# SingleSystem.net
KiCad netlist of a schematic drawn in EAGLE
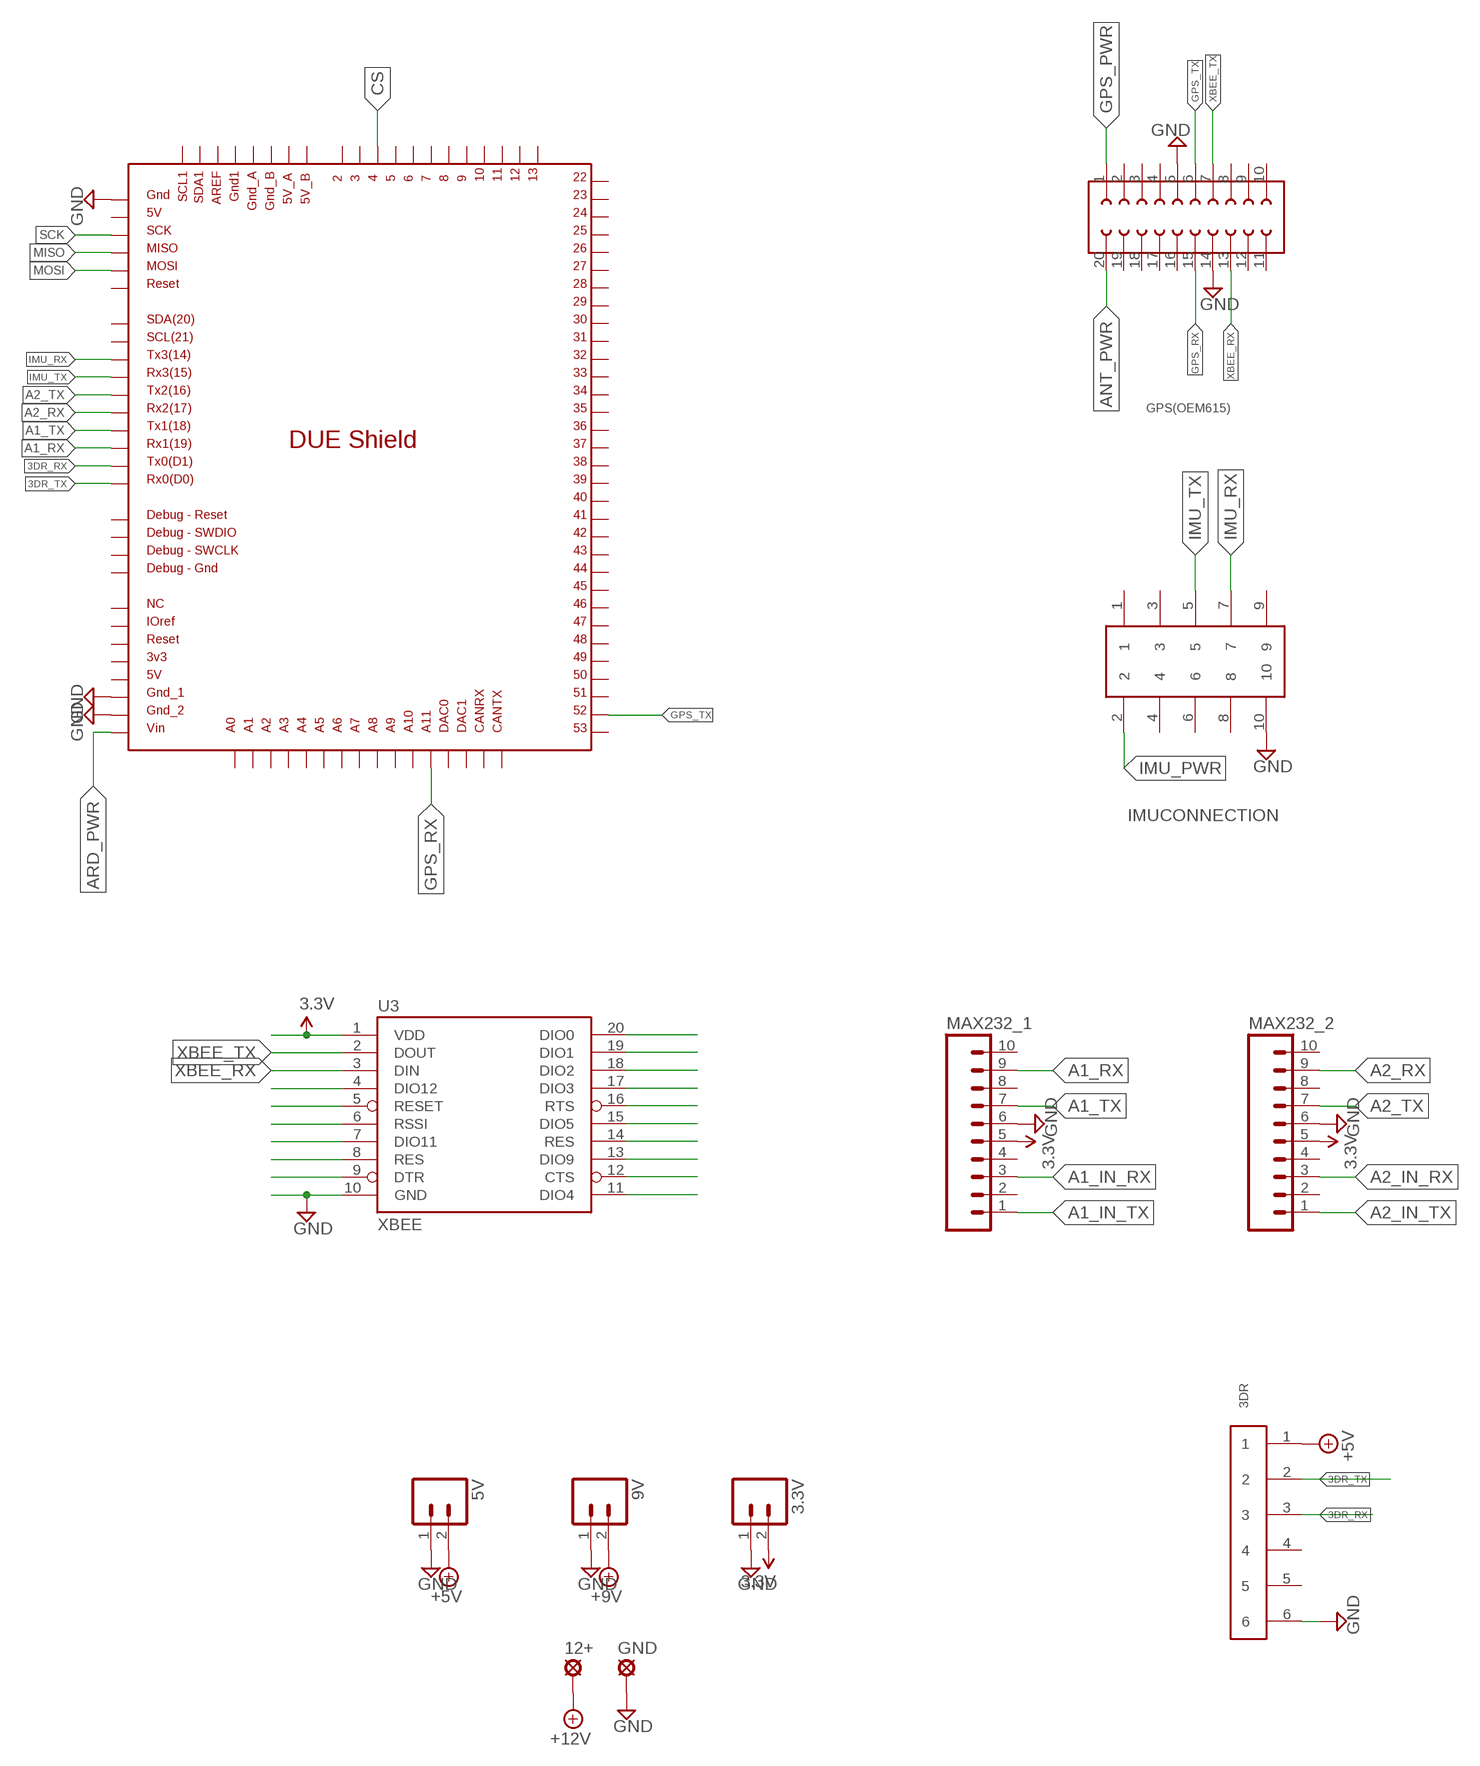
[diagram p0: schematic, sheet 1, part 1 of 2]
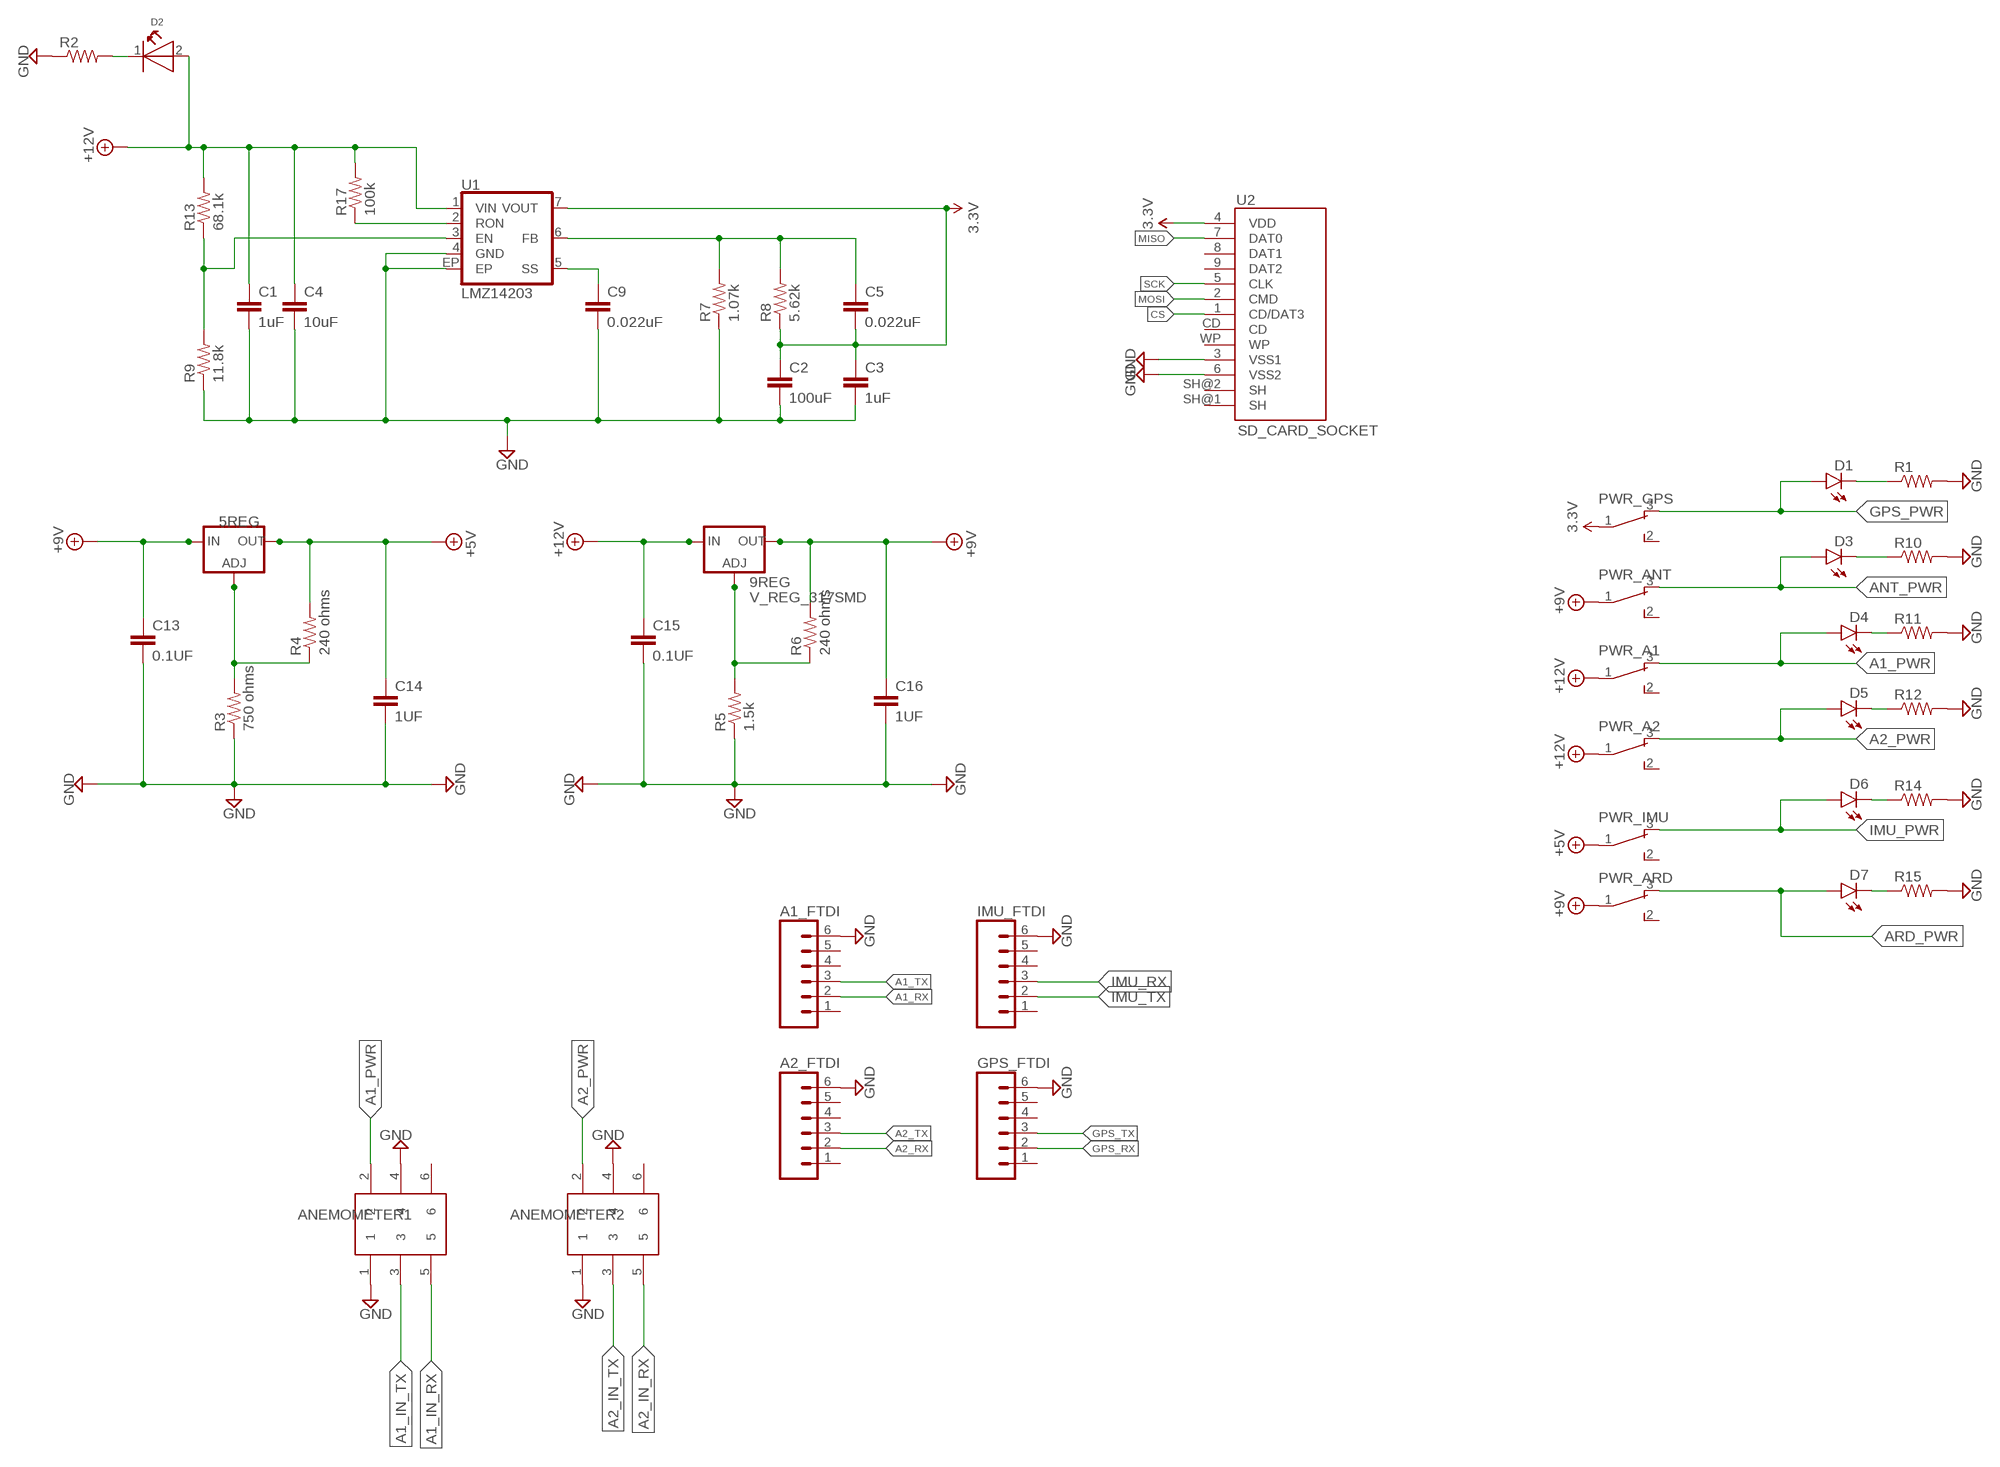
[diagram p1: schematic, sheet 1, part 2 of 2]

(export (version "E")
  (design (tool "Eeschema 10.0.6"))
  (components
    (comp (ref "3.3V")
      (value "M02")
      (footprint "eagle-import:02P")
      (libsource (lib "eagle-import") (part "M02"))
    )
    (comp (ref "3DR")
      (value "653006114822")
      (footprint "eagle-import:653006114822")
      (libsource (lib "eagle-import") (part "653006114822"))
    )
    (comp (ref "5REG")
      (value "V_REG_317SMD")
      (footprint "eagle-import:SOT223")
      (libsource (lib "eagle-import") (part "V_REG_317SMD"))
    )
    (comp (ref "5V")
      (value "M02")
      (footprint "eagle-import:02P")
      (libsource (lib "eagle-import") (part "M02"))
    )
    (comp (ref "9REG")
      (value "V_REG_317SMD")
      (footprint "eagle-import:SOT223")
      (libsource (lib "eagle-import") (part "V_REG_317SMD"))
    )
    (comp (ref "9V")
      (value "M02")
      (footprint "eagle-import:02P")
      (libsource (lib "eagle-import") (part "M02"))
    )
    (comp (ref "12+")
      (value "SE14")
      (footprint "eagle-import:SE14")
      (libsource (lib "eagle-import") (part "SE14"))
    )
    (comp (ref "A1_FTDI")
      (value "M06")
      (footprint "eagle-import:06P")
      (libsource (lib "eagle-import") (part "M06"))
    )
    (comp (ref "A2_FTDI")
      (value "M06")
      (footprint "eagle-import:06P")
      (libsource (lib "eagle-import") (part "M06"))
    )
    (comp (ref "ANEMOMETER1")
      (value "61200622323")
      (footprint "eagle-import:61200622323")
      (libsource (lib "eagle-import") (part "61200622323"))
    )
    (comp (ref "ANEMOMETER2")
      (value "61200622323")
      (footprint "eagle-import:61200622323")
      (libsource (lib "eagle-import") (part "61200622323"))
    )
    (comp (ref "C1")
      (value "1uF")
      (footprint "eagle-import:0805")
      (fields (field (name "MF") "VISHAY/SPRAGUE") (field (name "MPN") "1C10Z5U104M050R"))
      (libsource (lib "eagle-import") (part "1UF-25V-10%(0805)"))
    )
    (comp (ref "C2")
      (value "100uF")
      (footprint "eagle-import:1206")
      (libsource (lib "eagle-import") (part "CAP1206"))
    )
    (comp (ref "C3")
      (value "1uF")
      (footprint "eagle-import:0805")
      (fields (field (name "MF") "VISHAY/SPRAGUE") (field (name "MPN") "1C10Z5U104M050R"))
      (libsource (lib "eagle-import") (part "1UF-25V-10%(0805)"))
    )
    (comp (ref "C4")
      (value "10uF")
      (footprint "eagle-import:0805")
      (libsource (lib "eagle-import") (part "CAP0805"))
    )
    (comp (ref "C5")
      (value "0.022uF")
      (footprint "eagle-import:0603-CAP")
      (libsource (lib "eagle-import") (part "CAP0603-CAP"))
    )
    (comp (ref "C9")
      (value "0.022uF")
      (footprint "eagle-import:0603-CAP")
      (libsource (lib "eagle-import") (part "CAP0603-CAP"))
    )
    (comp (ref "C13")
      (value "0.1UF")
      (footprint "eagle-import:0805")
      (libsource (lib "eagle-import") (part "1UF-25V-10%(0805)"))
    )
    (comp (ref "C14")
      (value "1UF")
      (footprint "eagle-import:0805")
      (libsource (lib "eagle-import") (part "1UF-25V-10%(0805)"))
    )
    (comp (ref "C15")
      (value "0.1UF")
      (footprint "eagle-import:0805")
      (libsource (lib "eagle-import") (part "1UF-25V-10%(0805)"))
    )
    (comp (ref "C16")
      (value "1UF")
      (footprint "eagle-import:0805")
      (libsource (lib "eagle-import") (part "1UF-25V-10%(0805)"))
    )
    (comp (ref "D1")
      (value "LED-FKIT-1206")
      (footprint "eagle-import:FKIT-LED-1206")
      (libsource (lib "eagle-import") (part "LED-FKIT-1206"))
    )
    (comp (ref "D2")
      (value "WL-SMCW-150120BS75000-B")
      (footprint "eagle-import:1206")
      (fields
        (field (name "MANUFACTURER") "Würth Elektronik eiSos GmbH")
        (field (name "CREATED-BY") "Christin Otto")
      )
      (libsource (lib "eagle-import") (part "WL-SMCW-150120BS75000-B"))
    )
    (comp (ref "D3")
      (value "LED-FKIT-1206")
      (footprint "eagle-import:FKIT-LED-1206")
      (libsource (lib "eagle-import") (part "LED-FKIT-1206"))
    )
    (comp (ref "D4")
      (value "LED-FKIT-1206")
      (footprint "eagle-import:FKIT-LED-1206")
      (libsource (lib "eagle-import") (part "LED-FKIT-1206"))
    )
    (comp (ref "D5")
      (value "LED-FKIT-1206")
      (footprint "eagle-import:FKIT-LED-1206")
      (libsource (lib "eagle-import") (part "LED-FKIT-1206"))
    )
    (comp (ref "D6")
      (value "LED-FKIT-1206")
      (footprint "eagle-import:FKIT-LED-1206")
      (libsource (lib "eagle-import") (part "LED-FKIT-1206"))
    )
    (comp (ref "D7")
      (value "LED-FKIT-1206")
      (footprint "eagle-import:FKIT-LED-1206")
      (libsource (lib "eagle-import") (part "LED-FKIT-1206"))
    )
    (comp (ref "GND")
      (value "SE14")
      (footprint "eagle-import:SE14")
      (libsource (lib "eagle-import") (part "SE14"))
    )
    (comp (ref "GPS(OEM615)")
      (value "62002021821")
      (footprint "eagle-import:62002021821")
      (libsource (lib "eagle-import") (part "62002021821"))
    )
    (comp (ref "GPS_FTDI")
      (value "M06")
      (footprint "eagle-import:06P")
      (libsource (lib "eagle-import") (part "M06"))
    )
    (comp (ref "IMUCONNECTION")
      (value "62501021621")
      (footprint "eagle-import:62501021621")
      (libsource (lib "eagle-import") (part "62501021621"))
    )
    (comp (ref "IMU_FTDI")
      (value "M06")
      (footprint "eagle-import:06P")
      (libsource (lib "eagle-import") (part "M06"))
    )
    (comp (ref "MAX232_1")
      (value "M10")
      (footprint "eagle-import:10P")
      (libsource (lib "eagle-import") (part "M10"))
    )
    (comp (ref "MAX232_2")
      (value "M10")
      (footprint "eagle-import:10P")
      (libsource (lib "eagle-import") (part "M10"))
    )
    (comp (ref "PWR_A1")
      (value "450301014042")
      (footprint "eagle-import:450301014042")
      (libsource (lib "eagle-import") (part "450301014042"))
    )
    (comp (ref "PWR_A2")
      (value "450301014042")
      (footprint "eagle-import:450301014042")
      (libsource (lib "eagle-import") (part "450301014042"))
    )
    (comp (ref "PWR_ANT")
      (value "450301014042")
      (footprint "eagle-import:450301014042")
      (libsource (lib "eagle-import") (part "450301014042"))
    )
    (comp (ref "PWR_ARD")
      (value "450301014042")
      (footprint "eagle-import:450301014042")
      (libsource (lib "eagle-import") (part "450301014042"))
    )
    (comp (ref "PWR_GPS")
      (value "450301014042")
      (footprint "eagle-import:450301014042")
      (libsource (lib "eagle-import") (part "450301014042"))
    )
    (comp (ref "PWR_IMU")
      (value "450301014042")
      (footprint "eagle-import:450301014042")
      (libsource (lib "eagle-import") (part "450301014042"))
    )
    (comp (ref "R1")
      (value "R-US_M2012")
      (footprint "eagle-import:M2012")
      (libsource (lib "eagle-import") (part "R-US_M2012"))
    )
    (comp (ref "R2")
      (value "R-US_M2012")
      (footprint "eagle-import:M2012")
      (libsource (lib "eagle-import") (part "resistor_R-US_M2012"))
    )
    (comp (ref "R3")
      (value "750 ohms")
      (footprint "eagle-import:M2012")
      (libsource (lib "eagle-import") (part "R-US_M2012"))
    )
    (comp (ref "R4")
      (value "240 ohms")
      (footprint "eagle-import:M2012")
      (libsource (lib "eagle-import") (part "R-US_M2012"))
    )
    (comp (ref "R5")
      (value "1.5k")
      (footprint "eagle-import:M2012")
      (libsource (lib "eagle-import") (part "R-US_M2012"))
    )
    (comp (ref "R6")
      (value "240 ohms")
      (footprint "eagle-import:M2012")
      (libsource (lib "eagle-import") (part "R-US_M2012"))
    )
    (comp (ref "R7")
      (value "1.07k")
      (footprint "eagle-import:M2012")
      (libsource (lib "eagle-import") (part "resistor_R-US_M2012"))
    )
    (comp (ref "R8")
      (value "5.62k")
      (footprint "eagle-import:M2012")
      (libsource (lib "eagle-import") (part "resistor_R-US_M2012"))
    )
    (comp (ref "R9")
      (value "11.8k")
      (footprint "eagle-import:M2012")
      (libsource (lib "eagle-import") (part "resistor_R-US_M2012"))
    )
    (comp (ref "R10")
      (value "R-US_M2012")
      (footprint "eagle-import:M2012")
      (libsource (lib "eagle-import") (part "R-US_M2012"))
    )
    (comp (ref "R11")
      (value "R-US_M2012")
      (footprint "eagle-import:M2012")
      (libsource (lib "eagle-import") (part "R-US_M2012"))
    )
    (comp (ref "R12")
      (value "R-US_M2012")
      (footprint "eagle-import:M2012")
      (libsource (lib "eagle-import") (part "R-US_M2012"))
    )
    (comp (ref "R13")
      (value "68.1k")
      (footprint "eagle-import:M2012")
      (libsource (lib "eagle-import") (part "resistor_R-US_M2012"))
    )
    (comp (ref "R14")
      (value "R-US_M2012")
      (footprint "eagle-import:M2012")
      (libsource (lib "eagle-import") (part "R-US_M2012"))
    )
    (comp (ref "R15")
      (value "R-US_M2012")
      (footprint "eagle-import:M2012")
      (libsource (lib "eagle-import") (part "resistor_R-US_M2012"))
    )
    (comp (ref "R17")
      (value "100k")
      (footprint "eagle-import:M2012")
      (libsource (lib "eagle-import") (part "resistor_R-US_M2012"))
    )
    (comp (ref "U$1")
      (value "DUE(NORMAL)")
      (footprint "eagle-import:DUE(NORMAL)")
      (libsource (lib "eagle-import") (part "DUE(NORMAL)"))
    )
    (comp (ref "U1")
      (value "LMZ14203")
      (footprint "eagle-import:TO-PMOD-7")
      (libsource (lib "eagle-import") (part "LMZ14203"))
    )
    (comp (ref "U2")
      (value "SD_CARD_SOCKET")
      (footprint "eagle-import:SD_1_1")
      (libsource (lib "eagle-import") (part "SD_CARD_SOCKET"))
    )
    (comp (ref "U3")
      (value "XBEE")
      (footprint "eagle-import:XBEE-1")
      (libsource (lib "eagle-import") (part "XBEE-1B1"))
    )
  )
  (nets
    (net (code "1") (name "+5V") (class "Default")
      (node (ref "3DR") (pin "1") (pinfunction "1_1") (pintype "passive"))
      (node (ref "5REG") (pin "2") (pinfunction "OUT_2") (pintype "output"))
      (node (ref "5V") (pin "2") (pinfunction "2_2") (pintype "passive"))
      (node (ref "C14") (pin "1") (pinfunction "1_1") (pintype "passive"))
      (node (ref "PWR_IMU") (pin "1") (pinfunction "1_1") (pintype "passive"))
      (node (ref "R4") (pin "2") (pinfunction "2_2") (pintype "passive"))
    )
    (net (code "2") (name "+9V") (class "Default")
      (node (ref "5REG") (pin "3") (pinfunction "IN_3") (pintype "input"))
      (node (ref "9REG") (pin "2") (pinfunction "OUT_2") (pintype "output"))
      (node (ref "9V") (pin "2") (pinfunction "2_2") (pintype "passive"))
      (node (ref "C13") (pin "1") (pinfunction "1_1") (pintype "passive"))
      (node (ref "C16") (pin "1") (pinfunction "1_1") (pintype "passive"))
      (node (ref "PWR_ANT") (pin "1") (pinfunction "1_1") (pintype "passive"))
      (node (ref "PWR_ARD") (pin "1") (pinfunction "1_1") (pintype "passive"))
      (node (ref "R6") (pin "2") (pinfunction "2_2") (pintype "passive"))
    )
    (net (code "3") (name "+12V") (class "Default")
      (node (ref "12+") (pin "MP") (pinfunction "MP_MP") (pintype "passive"))
      (node (ref "9REG") (pin "3") (pinfunction "IN_3") (pintype "input"))
      (node (ref "C1") (pin "1") (pinfunction "1_1") (pintype "passive"))
      (node (ref "C15") (pin "1") (pinfunction "1_1") (pintype "passive"))
      (node (ref "C4") (pin "1") (pinfunction "1_1") (pintype "passive"))
      (node (ref "D2") (pin "2") (pinfunction "A_2") (pintype "bidirectional"))
      (node (ref "PWR_A1") (pin "1") (pinfunction "1_1") (pintype "passive"))
      (node (ref "PWR_A2") (pin "1") (pinfunction "1_1") (pintype "passive"))
      (node (ref "R13") (pin "2") (pinfunction "2_2") (pintype "passive"))
      (node (ref "R17") (pin "2") (pinfunction "2_2") (pintype "passive"))
      (node (ref "U1") (pin "1") (pinfunction "VIN_1") (pintype "bidirectional"))
    )
    (net (code "4") (name "3.3V") (class "Default")
      (node (ref "3.3V") (pin "2") (pinfunction "2_2") (pintype "passive"))
      (node (ref "C2") (pin "1") (pinfunction "1_1") (pintype "passive"))
      (node (ref "C3") (pin "1") (pinfunction "1_1") (pintype "passive"))
      (node (ref "C5") (pin "2") (pinfunction "2_2") (pintype "passive"))
      (node (ref "MAX232_1") (pin "5") (pinfunction "5_5") (pintype "passive"))
      (node (ref "MAX232_2") (pin "5") (pinfunction "5_5") (pintype "passive"))
      (node (ref "PWR_GPS") (pin "1") (pinfunction "1_1") (pintype "passive"))
      (node (ref "R8") (pin "1") (pinfunction "1_1") (pintype "passive"))
      (node (ref "U1") (pin "7") (pinfunction "VOUT_7") (pintype "bidirectional"))
      (node (ref "U2") (pin "4") (pinfunction "VDD_4") (pintype "power_in"))
      (node (ref "U3") (pin "1") (pinfunction "VDD_1") (pintype "power_in"))
    )
    (net (code "5") (name "3DR_RX") (class "Default")
      (node (ref "3DR") (pin "3") (pinfunction "3_3") (pintype "passive"))
      (node (ref "U$1") (pin "TX0") (pinfunction "TX0_TX0") (pintype "bidirectional"))
    )
    (net (code "6") (name "3DR_TX") (class "Default")
      (node (ref "3DR") (pin "2") (pinfunction "2_2") (pintype "passive"))
      (node (ref "U$1") (pin "RX0") (pinfunction "RX0_RX0") (pintype "bidirectional"))
    )
    (net (code "7") (name "A1_IN_RX") (class "Default")
      (node (ref "ANEMOMETER1") (pin "5") (pinfunction "5_5") (pintype "passive"))
      (node (ref "MAX232_1") (pin "3") (pinfunction "3_3") (pintype "passive"))
    )
    (net (code "8") (name "A1_IN_TX") (class "Default")
      (node (ref "ANEMOMETER1") (pin "3") (pinfunction "3_3") (pintype "passive"))
      (node (ref "MAX232_1") (pin "1") (pinfunction "1_1") (pintype "passive"))
    )
    (net (code "9") (name "A1_PWR") (class "Default")
      (node (ref "ANEMOMETER1") (pin "2") (pinfunction "2_2") (pintype "passive"))
      (node (ref "D4") (pin "A") (pinfunction "A_A") (pintype "passive"))
      (node (ref "PWR_A1") (pin "3") (pinfunction "3_3") (pintype "passive"))
    )
    (net (code "10") (name "A1_RX") (class "Default")
      (node (ref "A1_FTDI") (pin "2") (pinfunction "2_2") (pintype "passive"))
      (node (ref "MAX232_1") (pin "9") (pinfunction "9_9") (pintype "passive"))
      (node (ref "U$1") (pin "RX1") (pinfunction "RX1_RX1") (pintype "bidirectional"))
    )
    (net (code "11") (name "A1_TX") (class "Default")
      (node (ref "A1_FTDI") (pin "3") (pinfunction "3_3") (pintype "passive"))
      (node (ref "MAX232_1") (pin "7") (pinfunction "7_7") (pintype "passive"))
      (node (ref "U$1") (pin "TX1") (pinfunction "TX1_TX1") (pintype "bidirectional"))
    )
    (net (code "12") (name "A2_IN_RX") (class "Default")
      (node (ref "ANEMOMETER2") (pin "5") (pinfunction "5_5") (pintype "passive"))
      (node (ref "MAX232_2") (pin "3") (pinfunction "3_3") (pintype "passive"))
    )
    (net (code "13") (name "A2_IN_TX") (class "Default")
      (node (ref "ANEMOMETER2") (pin "3") (pinfunction "3_3") (pintype "passive"))
      (node (ref "MAX232_2") (pin "1") (pinfunction "1_1") (pintype "passive"))
    )
    (net (code "14") (name "A2_PWR") (class "Default")
      (node (ref "ANEMOMETER2") (pin "2") (pinfunction "2_2") (pintype "passive"))
      (node (ref "D5") (pin "A") (pinfunction "A_A") (pintype "passive"))
      (node (ref "PWR_A2") (pin "3") (pinfunction "3_3") (pintype "passive"))
    )
    (net (code "15") (name "A2_RX") (class "Default")
      (node (ref "A2_FTDI") (pin "2") (pinfunction "2_2") (pintype "passive"))
      (node (ref "MAX232_2") (pin "9") (pinfunction "9_9") (pintype "passive"))
      (node (ref "U$1") (pin "RX2") (pinfunction "RX2_RX2") (pintype "bidirectional"))
    )
    (net (code "16") (name "A2_TX") (class "Default")
      (node (ref "A2_FTDI") (pin "3") (pinfunction "3_3") (pintype "passive"))
      (node (ref "MAX232_2") (pin "7") (pinfunction "7_7") (pintype "passive"))
      (node (ref "U$1") (pin "TX2") (pinfunction "TX2_TX2") (pintype "bidirectional"))
    )
    (net (code "17") (name "ANT_PWR") (class "Default")
      (node (ref "D3") (pin "A") (pinfunction "A_A") (pintype "passive"))
      (node (ref "GPS(OEM615)") (pin "20") (pinfunction "20_20") (pintype "passive"))
      (node (ref "PWR_ANT") (pin "3") (pinfunction "3_3") (pintype "passive"))
    )
    (net (code "18") (name "ARD_PWR") (class "Default")
      (node (ref "D7") (pin "A") (pinfunction "A_A") (pintype "passive"))
      (node (ref "PWR_ARD") (pin "3") (pinfunction "3_3") (pintype "passive"))
      (node (ref "U$1") (pin "VIN") (pinfunction "VIN_VIN") (pintype "bidirectional"))
    )
    (net (code "19") (name "CS") (class "Default")
      (node (ref "U$1") (pin "4") (pinfunction "4_4") (pintype "bidirectional"))
      (node (ref "U2") (pin "1") (pinfunction "CD/DAT3_1") (pintype "bidirectional"))
    )
    (net (code "20") (name "GND") (class "Default")
      (node (ref "3.3V") (pin "1") (pinfunction "1_1") (pintype "passive"))
      (node (ref "3DR") (pin "6") (pinfunction "6_6") (pintype "passive"))
      (node (ref "5V") (pin "1") (pinfunction "1_1") (pintype "passive"))
      (node (ref "9V") (pin "1") (pinfunction "1_1") (pintype "passive"))
      (node (ref "A1_FTDI") (pin "6") (pinfunction "6_6") (pintype "passive"))
      (node (ref "A2_FTDI") (pin "6") (pinfunction "6_6") (pintype "passive"))
      (node (ref "ANEMOMETER1") (pin "1") (pinfunction "1_1") (pintype "passive"))
      (node (ref "ANEMOMETER1") (pin "4") (pinfunction "4_4") (pintype "passive"))
      (node (ref "ANEMOMETER2") (pin "1") (pinfunction "1_1") (pintype "passive"))
      (node (ref "ANEMOMETER2") (pin "4") (pinfunction "4_4") (pintype "passive"))
      (node (ref "C1") (pin "2") (pinfunction "2_2") (pintype "passive"))
      (node (ref "C13") (pin "2") (pinfunction "2_2") (pintype "passive"))
      (node (ref "C14") (pin "2") (pinfunction "2_2") (pintype "passive"))
      (node (ref "C15") (pin "2") (pinfunction "2_2") (pintype "passive"))
      (node (ref "C16") (pin "2") (pinfunction "2_2") (pintype "passive"))
      (node (ref "C2") (pin "2") (pinfunction "2_2") (pintype "passive"))
      (node (ref "C3") (pin "2") (pinfunction "2_2") (pintype "passive"))
      (node (ref "C4") (pin "2") (pinfunction "2_2") (pintype "passive"))
      (node (ref "C9") (pin "2") (pinfunction "2_2") (pintype "passive"))
      (node (ref "GND") (pin "MP") (pinfunction "MP_MP") (pintype "passive"))
      (node (ref "GPS(OEM615)") (pin "14") (pinfunction "14_14") (pintype "passive"))
      (node (ref "GPS(OEM615)") (pin "5") (pinfunction "5_5") (pintype "passive"))
      (node (ref "GPS_FTDI") (pin "6") (pinfunction "6_6") (pintype "passive"))
      (node (ref "IMUCONNECTION") (pin "10") (pinfunction "10_10") (pintype "passive"))
      (node (ref "IMU_FTDI") (pin "6") (pinfunction "6_6") (pintype "passive"))
      (node (ref "MAX232_1") (pin "6") (pinfunction "6_6") (pintype "passive"))
      (node (ref "MAX232_2") (pin "6") (pinfunction "6_6") (pintype "passive"))
      (node (ref "R1") (pin "2") (pinfunction "2_2") (pintype "passive"))
      (node (ref "R10") (pin "2") (pinfunction "2_2") (pintype "passive"))
      (node (ref "R11") (pin "2") (pinfunction "2_2") (pintype "passive"))
      (node (ref "R12") (pin "2") (pinfunction "2_2") (pintype "passive"))
      (node (ref "R14") (pin "2") (pinfunction "2_2") (pintype "passive"))
      (node (ref "R15") (pin "2") (pinfunction "2_2") (pintype "passive"))
      (node (ref "R2") (pin "1") (pinfunction "1_1") (pintype "passive"))
      (node (ref "R3") (pin "1") (pinfunction "1_1") (pintype "passive"))
      (node (ref "R5") (pin "1") (pinfunction "1_1") (pintype "passive"))
      (node (ref "R7") (pin "1") (pinfunction "1_1") (pintype "passive"))
      (node (ref "R9") (pin "1") (pinfunction "1_1") (pintype "passive"))
      (node (ref "U$1") (pin "5V_ICSP") (pinfunction "5V_ICSP_5V_ICSP") (pintype "bidirectional"))
      (node (ref "U$1") (pin "GND_1") (pinfunction "GND_1_GND_1") (pintype "bidirectional"))
      (node (ref "U$1") (pin "GND_2") (pinfunction "GND_2_GND_2") (pintype "bidirectional"))
      (node (ref "U1") (pin "4") (pinfunction "GND_4") (pintype "bidirectional"))
      (node (ref "U1") (pin "EP") (pinfunction "EP_EP") (pintype "bidirectional"))
      (node (ref "U2") (pin "3") (pinfunction "VSS1_3") (pintype "power_in"))
      (node (ref "U2") (pin "6") (pinfunction "VSS2_6") (pintype "power_in"))
      (node (ref "U3") (pin "10") (pinfunction "GND_10") (pintype "power_in"))
    )
    (net (code "21") (name "GPS_PWR") (class "Default")
      (node (ref "D1") (pin "A") (pinfunction "A_A") (pintype "passive"))
      (node (ref "GPS(OEM615)") (pin "1") (pinfunction "1_1") (pintype "passive"))
      (node (ref "PWR_GPS") (pin "3") (pinfunction "3_3") (pintype "passive"))
    )
    (net (code "22") (name "GPS_RX") (class "Default")
      (node (ref "GPS(OEM615)") (pin "15") (pinfunction "15_15") (pintype "passive"))
      (node (ref "GPS_FTDI") (pin "2") (pinfunction "2_2") (pintype "passive"))
      (node (ref "U$1") (pin "A11") (pinfunction "A11_A11") (pintype "bidirectional"))
    )
    (net (code "23") (name "GPS_TX") (class "Default")
      (node (ref "GPS(OEM615)") (pin "6") (pinfunction "6_6") (pintype "passive"))
      (node (ref "GPS_FTDI") (pin "3") (pinfunction "3_3") (pintype "passive"))
      (node (ref "U$1") (pin "52") (pinfunction "52_52") (pintype "bidirectional"))
    )
    (net (code "24") (name "IMU_PWR") (class "Default")
      (node (ref "D6") (pin "A") (pinfunction "A_A") (pintype "passive"))
      (node (ref "IMUCONNECTION") (pin "2") (pinfunction "2_2") (pintype "passive"))
      (node (ref "PWR_IMU") (pin "3") (pinfunction "3_3") (pintype "passive"))
    )
    (net (code "25") (name "IMU_RX") (class "Default")
      (node (ref "IMUCONNECTION") (pin "7") (pinfunction "7_7") (pintype "passive"))
      (node (ref "IMU_FTDI") (pin "3") (pinfunction "3_3") (pintype "passive"))
      (node (ref "U$1") (pin "TX3") (pinfunction "TX3_TX3") (pintype "bidirectional"))
    )
    (net (code "26") (name "IMU_TX") (class "Default")
      (node (ref "IMUCONNECTION") (pin "5") (pinfunction "5_5") (pintype "passive"))
      (node (ref "IMU_FTDI") (pin "2") (pinfunction "2_2") (pintype "passive"))
      (node (ref "U$1") (pin "RX3") (pinfunction "RX3_RX3") (pintype "bidirectional"))
    )
    (net (code "27") (name "MISO") (class "Default")
      (node (ref "U$1") (pin "MISO_ICSP") (pinfunction "MISO_ICSP_MISO_ICSP") (pintype "bidirectional"))
      (node (ref "U2") (pin "7") (pinfunction "DAT0_7") (pintype "bidirectional"))
    )
    (net (code "28") (name "MOSI") (class "Default")
      (node (ref "U$1") (pin "MOSI_ICSP") (pinfunction "MOSI_ICSP_MOSI_ICSP") (pintype "bidirectional"))
      (node (ref "U2") (pin "2") (pinfunction "CMD_2") (pintype "bidirectional"))
    )
    (net (code "29") (name "Net-(5REG-ADJ)") (class "Default")
      (node (ref "5REG") (pin "1") (pinfunction "ADJ_1") (pintype "input"))
      (node (ref "R3") (pin "2") (pinfunction "2_2") (pintype "passive"))
      (node (ref "R4") (pin "1") (pinfunction "1_1") (pintype "passive"))
    )
    (net (code "30") (name "Net-(9REG-ADJ)") (class "Default")
      (node (ref "9REG") (pin "1") (pinfunction "ADJ_1") (pintype "input"))
      (node (ref "R5") (pin "2") (pinfunction "2_2") (pintype "passive"))
      (node (ref "R6") (pin "1") (pinfunction "1_1") (pintype "passive"))
    )
    (net (code "31") (name "Net-(D1-PadC)") (class "Default")
      (node (ref "D1") (pin "C") (pinfunction "C_C") (pintype "passive"))
      (node (ref "R1") (pin "1") (pinfunction "1_1") (pintype "passive"))
    )
    (net (code "32") (name "Net-(D2-K)") (class "Default")
      (node (ref "D2") (pin "1") (pinfunction "K_1") (pintype "bidirectional"))
      (node (ref "R2") (pin "2") (pinfunction "2_2") (pintype "passive"))
    )
    (net (code "33") (name "Net-(D3-PadC)") (class "Default")
      (node (ref "D3") (pin "C") (pinfunction "C_C") (pintype "passive"))
      (node (ref "R10") (pin "1") (pinfunction "1_1") (pintype "passive"))
    )
    (net (code "34") (name "Net-(D4-PadC)") (class "Default")
      (node (ref "D4") (pin "C") (pinfunction "C_C") (pintype "passive"))
      (node (ref "R11") (pin "1") (pinfunction "1_1") (pintype "passive"))
    )
    (net (code "35") (name "Net-(D5-PadC)") (class "Default")
      (node (ref "D5") (pin "C") (pinfunction "C_C") (pintype "passive"))
      (node (ref "R12") (pin "1") (pinfunction "1_1") (pintype "passive"))
    )
    (net (code "36") (name "Net-(D6-PadC)") (class "Default")
      (node (ref "D6") (pin "C") (pinfunction "C_C") (pintype "passive"))
      (node (ref "R14") (pin "1") (pinfunction "1_1") (pintype "passive"))
    )
    (net (code "37") (name "Net-(D7-PadC)") (class "Default")
      (node (ref "D7") (pin "C") (pinfunction "C_C") (pintype "passive"))
      (node (ref "R15") (pin "1") (pinfunction "1_1") (pintype "passive"))
    )
    (net (code "38") (name "Net-(U1-EN)") (class "Default")
      (node (ref "R13") (pin "1") (pinfunction "1_1") (pintype "passive"))
      (node (ref "R9") (pin "2") (pinfunction "2_2") (pintype "passive"))
      (node (ref "U1") (pin "3") (pinfunction "EN_3") (pintype "bidirectional"))
    )
    (net (code "39") (name "Net-(U1-FB)") (class "Default")
      (node (ref "C5") (pin "1") (pinfunction "1_1") (pintype "passive"))
      (node (ref "R7") (pin "2") (pinfunction "2_2") (pintype "passive"))
      (node (ref "R8") (pin "2") (pinfunction "2_2") (pintype "passive"))
      (node (ref "U1") (pin "6") (pinfunction "FB_6") (pintype "bidirectional"))
    )
    (net (code "40") (name "Net-(U1-RON)") (class "Default")
      (node (ref "R17") (pin "1") (pinfunction "1_1") (pintype "passive"))
      (node (ref "U1") (pin "2") (pinfunction "RON_2") (pintype "bidirectional"))
    )
    (net (code "41") (name "Net-(U1-SS)") (class "Default")
      (node (ref "C9") (pin "1") (pinfunction "1_1") (pintype "passive"))
      (node (ref "U1") (pin "5") (pinfunction "SS_5") (pintype "bidirectional"))
    )
    (net (code "42") (name "SCK") (class "Default")
      (node (ref "U$1") (pin "SCK_ICSP") (pinfunction "SCK_ICSP_SCK_ICSP") (pintype "bidirectional"))
      (node (ref "U2") (pin "5") (pinfunction "CLK_5") (pintype "bidirectional"))
    )
    (net (code "43") (name "XBEE_RX") (class "Default")
      (node (ref "GPS(OEM615)") (pin "13") (pinfunction "13_13") (pintype "passive"))
      (node (ref "U3") (pin "3") (pinfunction "DIN_3") (pintype "input"))
    )
    (net (code "44") (name "XBEE_TX") (class "Default")
      (node (ref "GPS(OEM615)") (pin "7") (pinfunction "7_7") (pintype "passive"))
      (node (ref "U3") (pin "2") (pinfunction "DOUT_2") (pintype "output"))
    )
    (net (code "45") (name "unconnected-(3DR-Pad4)") (class "Default")
      (node (ref "3DR") (pin "4") (pinfunction "4_4") (pintype "passive"))
    )
    (net (code "46") (name "unconnected-(3DR-Pad5)") (class "Default")
      (node (ref "3DR") (pin "5") (pinfunction "5_5") (pintype "passive"))
    )
    (net (code "47") (name "unconnected-(A1_FTDI-Pad1)") (class "Default")
      (node (ref "A1_FTDI") (pin "1") (pinfunction "1_1") (pintype "passive"))
    )
    (net (code "48") (name "unconnected-(A1_FTDI-Pad4)") (class "Default")
      (node (ref "A1_FTDI") (pin "4") (pinfunction "4_4") (pintype "passive"))
    )
    (net (code "49") (name "unconnected-(A1_FTDI-Pad5)") (class "Default")
      (node (ref "A1_FTDI") (pin "5") (pinfunction "5_5") (pintype "passive"))
    )
    (net (code "50") (name "unconnected-(A2_FTDI-Pad1)") (class "Default")
      (node (ref "A2_FTDI") (pin "1") (pinfunction "1_1") (pintype "passive"))
    )
    (net (code "51") (name "unconnected-(A2_FTDI-Pad4)") (class "Default")
      (node (ref "A2_FTDI") (pin "4") (pinfunction "4_4") (pintype "passive"))
    )
    (net (code "52") (name "unconnected-(A2_FTDI-Pad5)") (class "Default")
      (node (ref "A2_FTDI") (pin "5") (pinfunction "5_5") (pintype "passive"))
    )
    (net (code "53") (name "unconnected-(ANEMOMETER1-Pad6)") (class "Default")
      (node (ref "ANEMOMETER1") (pin "6") (pinfunction "6_6") (pintype "passive"))
    )
    (net (code "54") (name "unconnected-(ANEMOMETER2-Pad6)") (class "Default")
      (node (ref "ANEMOMETER2") (pin "6") (pinfunction "6_6") (pintype "passive"))
    )
    (net (code "55") (name "unconnected-(GPS(OEM615)-Pad2)") (class "Default")
      (node (ref "GPS(OEM615)") (pin "2") (pinfunction "2_2") (pintype "passive"))
    )
    (net (code "56") (name "unconnected-(GPS(OEM615)-Pad3)") (class "Default")
      (node (ref "GPS(OEM615)") (pin "3") (pinfunction "3_3") (pintype "passive"))
    )
    (net (code "57") (name "unconnected-(GPS(OEM615)-Pad4)") (class "Default")
      (node (ref "GPS(OEM615)") (pin "4") (pinfunction "4_4") (pintype "passive"))
    )
    (net (code "58") (name "unconnected-(GPS(OEM615)-Pad8)") (class "Default")
      (node (ref "GPS(OEM615)") (pin "8") (pinfunction "8_8") (pintype "passive"))
    )
    (net (code "59") (name "unconnected-(GPS(OEM615)-Pad9)") (class "Default")
      (node (ref "GPS(OEM615)") (pin "9") (pinfunction "9_9") (pintype "passive"))
    )
    (net (code "60") (name "unconnected-(GPS(OEM615)-Pad10)") (class "Default")
      (node (ref "GPS(OEM615)") (pin "10") (pinfunction "10_10") (pintype "passive"))
    )
    (net (code "61") (name "unconnected-(GPS(OEM615)-Pad11)") (class "Default")
      (node (ref "GPS(OEM615)") (pin "11") (pinfunction "11_11") (pintype "passive"))
    )
    (net (code "62") (name "unconnected-(GPS(OEM615)-Pad12)") (class "Default")
      (node (ref "GPS(OEM615)") (pin "12") (pinfunction "12_12") (pintype "passive"))
    )
    (net (code "63") (name "unconnected-(GPS(OEM615)-Pad16)") (class "Default")
      (node (ref "GPS(OEM615)") (pin "16") (pinfunction "16_16") (pintype "passive"))
    )
    (net (code "64") (name "unconnected-(GPS(OEM615)-Pad17)") (class "Default")
      (node (ref "GPS(OEM615)") (pin "17") (pinfunction "17_17") (pintype "passive"))
    )
    (net (code "65") (name "unconnected-(GPS(OEM615)-Pad18)") (class "Default")
      (node (ref "GPS(OEM615)") (pin "18") (pinfunction "18_18") (pintype "passive"))
    )
    (net (code "66") (name "unconnected-(GPS(OEM615)-Pad19)") (class "Default")
      (node (ref "GPS(OEM615)") (pin "19") (pinfunction "19_19") (pintype "passive"))
    )
    (net (code "67") (name "unconnected-(GPS_FTDI-Pad1)") (class "Default")
      (node (ref "GPS_FTDI") (pin "1") (pinfunction "1_1") (pintype "passive"))
    )
    (net (code "68") (name "unconnected-(GPS_FTDI-Pad4)") (class "Default")
      (node (ref "GPS_FTDI") (pin "4") (pinfunction "4_4") (pintype "passive"))
    )
    (net (code "69") (name "unconnected-(GPS_FTDI-Pad5)") (class "Default")
      (node (ref "GPS_FTDI") (pin "5") (pinfunction "5_5") (pintype "passive"))
    )
    (net (code "70") (name "unconnected-(IMUCONNECTION-Pad1)") (class "Default")
      (node (ref "IMUCONNECTION") (pin "1") (pinfunction "1_1") (pintype "passive"))
    )
    (net (code "71") (name "unconnected-(IMUCONNECTION-Pad3)") (class "Default")
      (node (ref "IMUCONNECTION") (pin "3") (pinfunction "3_3") (pintype "passive"))
    )
    (net (code "72") (name "unconnected-(IMUCONNECTION-Pad4)") (class "Default")
      (node (ref "IMUCONNECTION") (pin "4") (pinfunction "4_4") (pintype "passive"))
    )
    (net (code "73") (name "unconnected-(IMUCONNECTION-Pad6)") (class "Default")
      (node (ref "IMUCONNECTION") (pin "6") (pinfunction "6_6") (pintype "passive"))
    )
    (net (code "74") (name "unconnected-(IMUCONNECTION-Pad8)") (class "Default")
      (node (ref "IMUCONNECTION") (pin "8") (pinfunction "8_8") (pintype "passive"))
    )
    (net (code "75") (name "unconnected-(IMUCONNECTION-Pad9)") (class "Default")
      (node (ref "IMUCONNECTION") (pin "9") (pinfunction "9_9") (pintype "passive"))
    )
    (net (code "76") (name "unconnected-(IMU_FTDI-Pad1)") (class "Default")
      (node (ref "IMU_FTDI") (pin "1") (pinfunction "1_1") (pintype "passive"))
    )
    (net (code "77") (name "unconnected-(IMU_FTDI-Pad4)") (class "Default")
      (node (ref "IMU_FTDI") (pin "4") (pinfunction "4_4") (pintype "passive"))
    )
    (net (code "78") (name "unconnected-(IMU_FTDI-Pad5)") (class "Default")
      (node (ref "IMU_FTDI") (pin "5") (pinfunction "5_5") (pintype "passive"))
    )
    (net (code "79") (name "unconnected-(MAX232_1-Pad2)") (class "Default")
      (node (ref "MAX232_1") (pin "2") (pinfunction "2_2") (pintype "passive"))
    )
    (net (code "80") (name "unconnected-(MAX232_1-Pad4)") (class "Default")
      (node (ref "MAX232_1") (pin "4") (pinfunction "4_4") (pintype "passive"))
    )
    (net (code "81") (name "unconnected-(MAX232_1-Pad8)") (class "Default")
      (node (ref "MAX232_1") (pin "8") (pinfunction "8_8") (pintype "passive"))
    )
    (net (code "82") (name "unconnected-(MAX232_1-Pad10)") (class "Default")
      (node (ref "MAX232_1") (pin "10") (pinfunction "10_10") (pintype "passive"))
    )
    (net (code "83") (name "unconnected-(MAX232_2-Pad2)") (class "Default")
      (node (ref "MAX232_2") (pin "2") (pinfunction "2_2") (pintype "passive"))
    )
    (net (code "84") (name "unconnected-(MAX232_2-Pad4)") (class "Default")
      (node (ref "MAX232_2") (pin "4") (pinfunction "4_4") (pintype "passive"))
    )
    (net (code "85") (name "unconnected-(MAX232_2-Pad8)") (class "Default")
      (node (ref "MAX232_2") (pin "8") (pinfunction "8_8") (pintype "passive"))
    )
    (net (code "86") (name "unconnected-(MAX232_2-Pad10)") (class "Default")
      (node (ref "MAX232_2") (pin "10") (pinfunction "10_10") (pintype "passive"))
    )
    (net (code "87") (name "unconnected-(PWR_A1-Pad2)") (class "Default")
      (node (ref "PWR_A1") (pin "2") (pinfunction "2_2") (pintype "passive"))
    )
    (net (code "88") (name "unconnected-(PWR_A2-Pad2)") (class "Default")
      (node (ref "PWR_A2") (pin "2") (pinfunction "2_2") (pintype "passive"))
    )
    (net (code "89") (name "unconnected-(PWR_ANT-Pad2)") (class "Default")
      (node (ref "PWR_ANT") (pin "2") (pinfunction "2_2") (pintype "passive"))
    )
    (net (code "90") (name "unconnected-(PWR_ARD-Pad2)") (class "Default")
      (node (ref "PWR_ARD") (pin "2") (pinfunction "2_2") (pintype "passive"))
    )
    (net (code "91") (name "unconnected-(PWR_GPS-Pad2)") (class "Default")
      (node (ref "PWR_GPS") (pin "2") (pinfunction "2_2") (pintype "passive"))
    )
    (net (code "92") (name "unconnected-(PWR_IMU-Pad2)") (class "Default")
      (node (ref "PWR_IMU") (pin "2") (pinfunction "2_2") (pintype "passive"))
    )
    (net (code "93") (name "unconnected-(U$1-Pad2)") (class "Default")
      (node (ref "U$1") (pin "2") (pinfunction "2_2") (pintype "bidirectional"))
    )
    (net (code "94") (name "unconnected-(U$1-Pad3)") (class "Default")
      (node (ref "U$1") (pin "3") (pinfunction "3_3") (pintype "bidirectional"))
    )
    (net (code "95") (name "unconnected-(U$1-Pad3V3)") (class "Default")
      (node (ref "U$1") (pin "3V3") (pinfunction "3V3_3V3") (pintype "bidirectional"))
    )
    (net (code "96") (name "unconnected-(U$1-Pad5)") (class "Default")
      (node (ref "U$1") (pin "5") (pinfunction "5_5") (pintype "bidirectional"))
    )
    (net (code "97") (name "unconnected-(U$1-Pad5V)") (class "Default")
      (node (ref "U$1") (pin "5V") (pinfunction "5V_5V") (pintype "bidirectional"))
    )
    (net (code "98") (name "unconnected-(U$1-Pad5V_A)") (class "Default")
      (node (ref "U$1") (pin "5V_A") (pinfunction "5V_A_5V_A") (pintype "bidirectional"))
    )
    (net (code "99") (name "unconnected-(U$1-Pad5V_B)") (class "Default")
      (node (ref "U$1") (pin "5V_B") (pinfunction "5V_B_5V_B") (pintype "bidirectional"))
    )
    (net (code "100") (name "unconnected-(U$1-Pad6)") (class "Default")
      (node (ref "U$1") (pin "6") (pinfunction "6_6") (pintype "bidirectional"))
    )
    (net (code "101") (name "unconnected-(U$1-Pad7)") (class "Default")
      (node (ref "U$1") (pin "7") (pinfunction "7_7") (pintype "bidirectional"))
    )
    (net (code "102") (name "unconnected-(U$1-Pad8)") (class "Default")
      (node (ref "U$1") (pin "8") (pinfunction "8_8") (pintype "bidirectional"))
    )
    (net (code "103") (name "unconnected-(U$1-Pad9)") (class "Default")
      (node (ref "U$1") (pin "9") (pinfunction "9_9") (pintype "bidirectional"))
    )
    (net (code "104") (name "unconnected-(U$1-Pad10)") (class "Default")
      (node (ref "U$1") (pin "10") (pinfunction "10_10") (pintype "bidirectional"))
    )
    (net (code "105") (name "unconnected-(U$1-Pad11)") (class "Default")
      (node (ref "U$1") (pin "11") (pinfunction "11_11") (pintype "bidirectional"))
    )
    (net (code "106") (name "unconnected-(U$1-Pad12)") (class "Default")
      (node (ref "U$1") (pin "12") (pinfunction "12_12") (pintype "bidirectional"))
    )
    (net (code "107") (name "unconnected-(U$1-Pad13)") (class "Default")
      (node (ref "U$1") (pin "13") (pinfunction "13_13") (pintype "bidirectional"))
    )
    (net (code "108") (name "unconnected-(U$1-Pad22)") (class "Default")
      (node (ref "U$1") (pin "22") (pinfunction "22_22") (pintype "bidirectional"))
    )
    (net (code "109") (name "unconnected-(U$1-Pad23)") (class "Default")
      (node (ref "U$1") (pin "23") (pinfunction "23_23") (pintype "bidirectional"))
    )
    (net (code "110") (name "unconnected-(U$1-Pad24)") (class "Default")
      (node (ref "U$1") (pin "24") (pinfunction "24_24") (pintype "bidirectional"))
    )
    (net (code "111") (name "unconnected-(U$1-Pad25)") (class "Default")
      (node (ref "U$1") (pin "25") (pinfunction "25_25") (pintype "bidirectional"))
    )
    (net (code "112") (name "unconnected-(U$1-Pad26)") (class "Default")
      (node (ref "U$1") (pin "26") (pinfunction "26_26") (pintype "bidirectional"))
    )
    (net (code "113") (name "unconnected-(U$1-Pad27)") (class "Default")
      (node (ref "U$1") (pin "27") (pinfunction "27_27") (pintype "bidirectional"))
    )
    (net (code "114") (name "unconnected-(U$1-Pad28)") (class "Default")
      (node (ref "U$1") (pin "28") (pinfunction "28_28") (pintype "bidirectional"))
    )
    (net (code "115") (name "unconnected-(U$1-Pad29)") (class "Default")
      (node (ref "U$1") (pin "29") (pinfunction "29_29") (pintype "bidirectional"))
    )
    (net (code "116") (name "unconnected-(U$1-Pad30)") (class "Default")
      (node (ref "U$1") (pin "30") (pinfunction "30_30") (pintype "bidirectional"))
    )
    (net (code "117") (name "unconnected-(U$1-Pad31)") (class "Default")
      (node (ref "U$1") (pin "31") (pinfunction "31_31") (pintype "bidirectional"))
    )
    (net (code "118") (name "unconnected-(U$1-Pad32)") (class "Default")
      (node (ref "U$1") (pin "32") (pinfunction "32_32") (pintype "bidirectional"))
    )
    (net (code "119") (name "unconnected-(U$1-Pad33)") (class "Default")
      (node (ref "U$1") (pin "33") (pinfunction "33_33") (pintype "bidirectional"))
    )
    (net (code "120") (name "unconnected-(U$1-Pad34)") (class "Default")
      (node (ref "U$1") (pin "34") (pinfunction "34_34") (pintype "bidirectional"))
    )
    (net (code "121") (name "unconnected-(U$1-Pad35)") (class "Default")
      (node (ref "U$1") (pin "35") (pinfunction "35_35") (pintype "bidirectional"))
    )
    (net (code "122") (name "unconnected-(U$1-Pad36)") (class "Default")
      (node (ref "U$1") (pin "36") (pinfunction "36_36") (pintype "bidirectional"))
    )
    (net (code "123") (name "unconnected-(U$1-Pad37)") (class "Default")
      (node (ref "U$1") (pin "37") (pinfunction "37_37") (pintype "bidirectional"))
    )
    (net (code "124") (name "unconnected-(U$1-Pad38)") (class "Default")
      (node (ref "U$1") (pin "38") (pinfunction "38_38") (pintype "bidirectional"))
    )
    (net (code "125") (name "unconnected-(U$1-Pad39)") (class "Default")
      (node (ref "U$1") (pin "39") (pinfunction "39_39") (pintype "bidirectional"))
    )
    (net (code "126") (name "unconnected-(U$1-Pad40)") (class "Default")
      (node (ref "U$1") (pin "40") (pinfunction "40_40") (pintype "bidirectional"))
    )
    (net (code "127") (name "unconnected-(U$1-Pad41)") (class "Default")
      (node (ref "U$1") (pin "41") (pinfunction "41_41") (pintype "bidirectional"))
    )
    (net (code "128") (name "unconnected-(U$1-Pad42)") (class "Default")
      (node (ref "U$1") (pin "42") (pinfunction "42_42") (pintype "bidirectional"))
    )
    (net (code "129") (name "unconnected-(U$1-Pad43)") (class "Default")
      (node (ref "U$1") (pin "43") (pinfunction "43_43") (pintype "bidirectional"))
    )
    (net (code "130") (name "unconnected-(U$1-Pad44)") (class "Default")
      (node (ref "U$1") (pin "44") (pinfunction "44_44") (pintype "bidirectional"))
    )
    (net (code "131") (name "unconnected-(U$1-Pad45)") (class "Default")
      (node (ref "U$1") (pin "45") (pinfunction "45_45") (pintype "bidirectional"))
    )
    (net (code "132") (name "unconnected-(U$1-Pad46)") (class "Default")
      (node (ref "U$1") (pin "46") (pinfunction "46_46") (pintype "bidirectional"))
    )
    (net (code "133") (name "unconnected-(U$1-Pad47)") (class "Default")
      (node (ref "U$1") (pin "47") (pinfunction "47_47") (pintype "bidirectional"))
    )
    (net (code "134") (name "unconnected-(U$1-Pad48)") (class "Default")
      (node (ref "U$1") (pin "48") (pinfunction "48_48") (pintype "bidirectional"))
    )
    (net (code "135") (name "unconnected-(U$1-Pad49)") (class "Default")
      (node (ref "U$1") (pin "49") (pinfunction "49_49") (pintype "bidirectional"))
    )
    (net (code "136") (name "unconnected-(U$1-Pad50)") (class "Default")
      (node (ref "U$1") (pin "50") (pinfunction "50_50") (pintype "bidirectional"))
    )
    (net (code "137") (name "unconnected-(U$1-Pad51)") (class "Default")
      (node (ref "U$1") (pin "51") (pinfunction "51_51") (pintype "bidirectional"))
    )
    (net (code "138") (name "unconnected-(U$1-Pad53)") (class "Default")
      (node (ref "U$1") (pin "53") (pinfunction "53_53") (pintype "bidirectional"))
    )
    (net (code "139") (name "unconnected-(U$1-PadA0)") (class "Default")
      (node (ref "U$1") (pin "A0") (pinfunction "A0_A0") (pintype "bidirectional"))
    )
    (net (code "140") (name "unconnected-(U$1-PadA1)") (class "Default")
      (node (ref "U$1") (pin "A1") (pinfunction "A1_A1") (pintype "bidirectional"))
    )
    (net (code "141") (name "unconnected-(U$1-PadA2)") (class "Default")
      (node (ref "U$1") (pin "A2") (pinfunction "A2_A2") (pintype "bidirectional"))
    )
    (net (code "142") (name "unconnected-(U$1-PadA3)") (class "Default")
      (node (ref "U$1") (pin "A3") (pinfunction "A3_A3") (pintype "bidirectional"))
    )
    (net (code "143") (name "unconnected-(U$1-PadA4)") (class "Default")
      (node (ref "U$1") (pin "A4") (pinfunction "A4_A4") (pintype "bidirectional"))
    )
    (net (code "144") (name "unconnected-(U$1-PadA5)") (class "Default")
      (node (ref "U$1") (pin "A5") (pinfunction "A5_A5") (pintype "bidirectional"))
    )
    (net (code "145") (name "unconnected-(U$1-PadA6)") (class "Default")
      (node (ref "U$1") (pin "A6") (pinfunction "A6_A6") (pintype "bidirectional"))
    )
    (net (code "146") (name "unconnected-(U$1-PadA7)") (class "Default")
      (node (ref "U$1") (pin "A7") (pinfunction "A7_A7") (pintype "bidirectional"))
    )
    (net (code "147") (name "unconnected-(U$1-PadA8)") (class "Default")
      (node (ref "U$1") (pin "A8") (pinfunction "A8_A8") (pintype "bidirectional"))
    )
    (net (code "148") (name "unconnected-(U$1-PadA9)") (class "Default")
      (node (ref "U$1") (pin "A9") (pinfunction "A9_A9") (pintype "bidirectional"))
    )
    (net (code "149") (name "unconnected-(U$1-PadA10)") (class "Default")
      (node (ref "U$1") (pin "A10") (pinfunction "A10_A10") (pintype "bidirectional"))
    )
    (net (code "150") (name "unconnected-(U$1-PadAREF)") (class "Default")
      (node (ref "U$1") (pin "AREF") (pinfunction "AREF_AREF") (pintype "bidirectional"))
    )
    (net (code "151") (name "unconnected-(U$1-PadCANRX)") (class "Default")
      (node (ref "U$1") (pin "CANRX") (pinfunction "CANRX_CANRX") (pintype "bidirectional"))
    )
    (net (code "152") (name "unconnected-(U$1-PadCANTX)") (class "Default")
      (node (ref "U$1") (pin "CANTX") (pinfunction "CANTX_CANTX") (pintype "bidirectional"))
    )
    (net (code "153") (name "unconnected-(U$1-PadDAC0)") (class "Default")
      (node (ref "U$1") (pin "DAC0") (pinfunction "DAC0_DAC0") (pintype "bidirectional"))
    )
    (net (code "154") (name "unconnected-(U$1-PadDAC1)") (class "Default")
      (node (ref "U$1") (pin "DAC1") (pinfunction "DAC1_DAC1") (pintype "bidirectional"))
    )
    (net (code "155") (name "unconnected-(U$1-PadGND1)") (class "Default")
      (node (ref "U$1") (pin "GND1") (pinfunction "GND1_GND1") (pintype "bidirectional"))
    )
    (net (code "156") (name "unconnected-(U$1-PadGND_A)") (class "Default")
      (node (ref "U$1") (pin "GND_A") (pinfunction "GND_A_GND_A") (pintype "bidirectional"))
    )
    (net (code "157") (name "unconnected-(U$1-PadGND_B)") (class "Default")
      (node (ref "U$1") (pin "GND_B") (pinfunction "GND_B_GND_B") (pintype "bidirectional"))
    )
    (net (code "158") (name "unconnected-(U$1-PadGND_DEBUG)") (class "Default")
      (node (ref "U$1") (pin "GND_DEBUG") (pinfunction "GND_DEBUG_GND_DEBUG") (pintype "bidirectional"))
    )
    (net (code "159") (name "unconnected-(U$1-PadGND_ICSP)") (class "Default")
      (node (ref "U$1") (pin "GND_ICSP") (pinfunction "GND_ICSP_GND_ICSP") (pintype "bidirectional"))
    )
    (net (code "160") (name "unconnected-(U$1-PadIOREF)") (class "Default")
      (node (ref "U$1") (pin "IOREF") (pinfunction "IOREF_IOREF") (pintype "bidirectional"))
    )
    (net (code "161") (name "unconnected-(U$1-PadNC)") (class "Default")
      (node (ref "U$1") (pin "NC") (pinfunction "NC_NC") (pintype "bidirectional"))
    )
    (net (code "162") (name "unconnected-(U$1-PadRESET)") (class "Default")
      (node (ref "U$1") (pin "RESET") (pinfunction "RESET_RESET") (pintype "bidirectional"))
    )
    (net (code "163") (name "unconnected-(U$1-PadRESET_DEBUG)") (class "Default")
      (node (ref "U$1") (pin "RESET_DEBUG") (pinfunction "RESET_DEBUG_RESET_DEBUG") (pintype "bidirectional"))
    )
    (net (code "164") (name "unconnected-(U$1-PadRESET_ICSP)") (class "Default")
      (node (ref "U$1") (pin "RESET_ICSP") (pinfunction "RESET_ICSP_RESET_ICSP") (pintype "bidirectional"))
    )
    (net (code "165") (name "unconnected-(U$1-PadSCL)") (class "Default")
      (node (ref "U$1") (pin "SCL") (pinfunction "SCL_SCL") (pintype "bidirectional"))
    )
    (net (code "166") (name "unconnected-(U$1-PadSCL1)") (class "Default")
      (node (ref "U$1") (pin "SCL1") (pinfunction "SCL1_SCL1") (pintype "bidirectional"))
    )
    (net (code "167") (name "unconnected-(U$1-PadSDA)") (class "Default")
      (node (ref "U$1") (pin "SDA") (pinfunction "SDA_SDA") (pintype "bidirectional"))
    )
    (net (code "168") (name "unconnected-(U$1-PadSDA1)") (class "Default")
      (node (ref "U$1") (pin "SDA1") (pinfunction "SDA1_SDA1") (pintype "bidirectional"))
    )
    (net (code "169") (name "unconnected-(U$1-PadSWCLK_DEBUG)") (class "Default")
      (node (ref "U$1") (pin "SWCLK_DEBUG") (pinfunction "SWCLK_DEBUG_SWCLK_DEBUG") (pintype "bidirectional"))
    )
    (net (code "170") (name "unconnected-(U$1-PadSWDIO_DEBUG)") (class "Default")
      (node (ref "U$1") (pin "SWDIO_DEBUG") (pinfunction "SWDIO_DEBUG_SWDIO_DEBUG") (pintype "bidirectional"))
    )
    (net (code "171") (name "unconnected-(U2-DAT1-Pad8)") (class "Default")
      (node (ref "U2") (pin "8") (pinfunction "DAT1_8") (pintype "bidirectional"))
    )
    (net (code "172") (name "unconnected-(U2-DAT2-Pad9)") (class "Default")
      (node (ref "U2") (pin "9") (pinfunction "DAT2_9") (pintype "bidirectional"))
    )
    (net (code "173") (name "unconnected-(U2-PadCD)") (class "Default")
      (node (ref "U2") (pin "CD") (pinfunction "CD_CD") (pintype "bidirectional"))
    )
    (net (code "174") (name "unconnected-(U2-PadWP)") (class "Default")
      (node (ref "U2") (pin "WP") (pinfunction "WP_WP") (pintype "bidirectional"))
    )
    (net (code "175") (name "unconnected-(U2-SH-PadSH@1)") (class "Default")
      (node (ref "U2") (pin "SH@1") (pinfunction "SH_SH@1") (pintype "bidirectional"))
    )
    (net (code "176") (name "unconnected-(U2-SH-PadSH@2)") (class "Default")
      (node (ref "U2") (pin "SH@2") (pinfunction "SH_SH@2") (pintype "bidirectional"))
    )
    (net (code "177") (name "unconnected-(U3-CTS-Pad12)") (class "Default")
      (node (ref "U3") (pin "12") (pinfunction "CTS_12") (pintype "output"))
    )
    (net (code "178") (name "unconnected-(U3-DIO0-Pad20)") (class "Default")
      (node (ref "U3") (pin "20") (pinfunction "DIO0_20") (pintype "bidirectional"))
    )
    (net (code "179") (name "unconnected-(U3-DIO1-Pad19)") (class "Default")
      (node (ref "U3") (pin "19") (pinfunction "DIO1_19") (pintype "bidirectional"))
    )
    (net (code "180") (name "unconnected-(U3-DIO2-Pad18)") (class "Default")
      (node (ref "U3") (pin "18") (pinfunction "DIO2_18") (pintype "bidirectional"))
    )
    (net (code "181") (name "unconnected-(U3-DIO3-Pad17)") (class "Default")
      (node (ref "U3") (pin "17") (pinfunction "DIO3_17") (pintype "bidirectional"))
    )
    (net (code "182") (name "unconnected-(U3-DIO4-Pad11)") (class "Default")
      (node (ref "U3") (pin "11") (pinfunction "DIO4_11") (pintype "bidirectional"))
    )
    (net (code "183") (name "unconnected-(U3-DIO5-Pad15)") (class "Default")
      (node (ref "U3") (pin "15") (pinfunction "DIO5_15") (pintype "bidirectional"))
    )
    (net (code "184") (name "unconnected-(U3-DIO9-Pad13)") (class "Default")
      (node (ref "U3") (pin "13") (pinfunction "DIO9_13") (pintype "bidirectional"))
    )
    (net (code "185") (name "unconnected-(U3-DIO11-Pad7)") (class "Default")
      (node (ref "U3") (pin "7") (pinfunction "DIO11_7") (pintype "bidirectional"))
    )
    (net (code "186") (name "unconnected-(U3-DIO12-Pad4)") (class "Default")
      (node (ref "U3") (pin "4") (pinfunction "DIO12_4") (pintype "bidirectional"))
    )
    (net (code "187") (name "unconnected-(U3-DTR-Pad9)") (class "Default")
      (node (ref "U3") (pin "9") (pinfunction "DTR_9") (pintype "bidirectional"))
    )
    (net (code "188") (name "unconnected-(U3-RES-Pad8)") (class "Default")
      (node (ref "U3") (pin "8") (pinfunction "RES_8") (pintype "bidirectional"))
    )
    (net (code "189") (name "unconnected-(U3-RES-Pad14)") (class "Default")
      (node (ref "U3") (pin "14") (pinfunction "RES_14") (pintype "bidirectional"))
    )
    (net (code "190") (name "unconnected-(U3-RESET-Pad5)") (class "Default")
      (node (ref "U3") (pin "5") (pinfunction "RESET_5") (pintype "input"))
    )
    (net (code "191") (name "unconnected-(U3-RSSI-Pad6)") (class "Default")
      (node (ref "U3") (pin "6") (pinfunction "RSSI_6") (pintype "bidirectional"))
    )
    (net (code "192") (name "unconnected-(U3-RTS-Pad16)") (class "Default")
      (node (ref "U3") (pin "16") (pinfunction "RTS_16") (pintype "input"))
    )
  )
)
